# Bridge.net
KiCad netlist of a schematic drawn in EAGLE
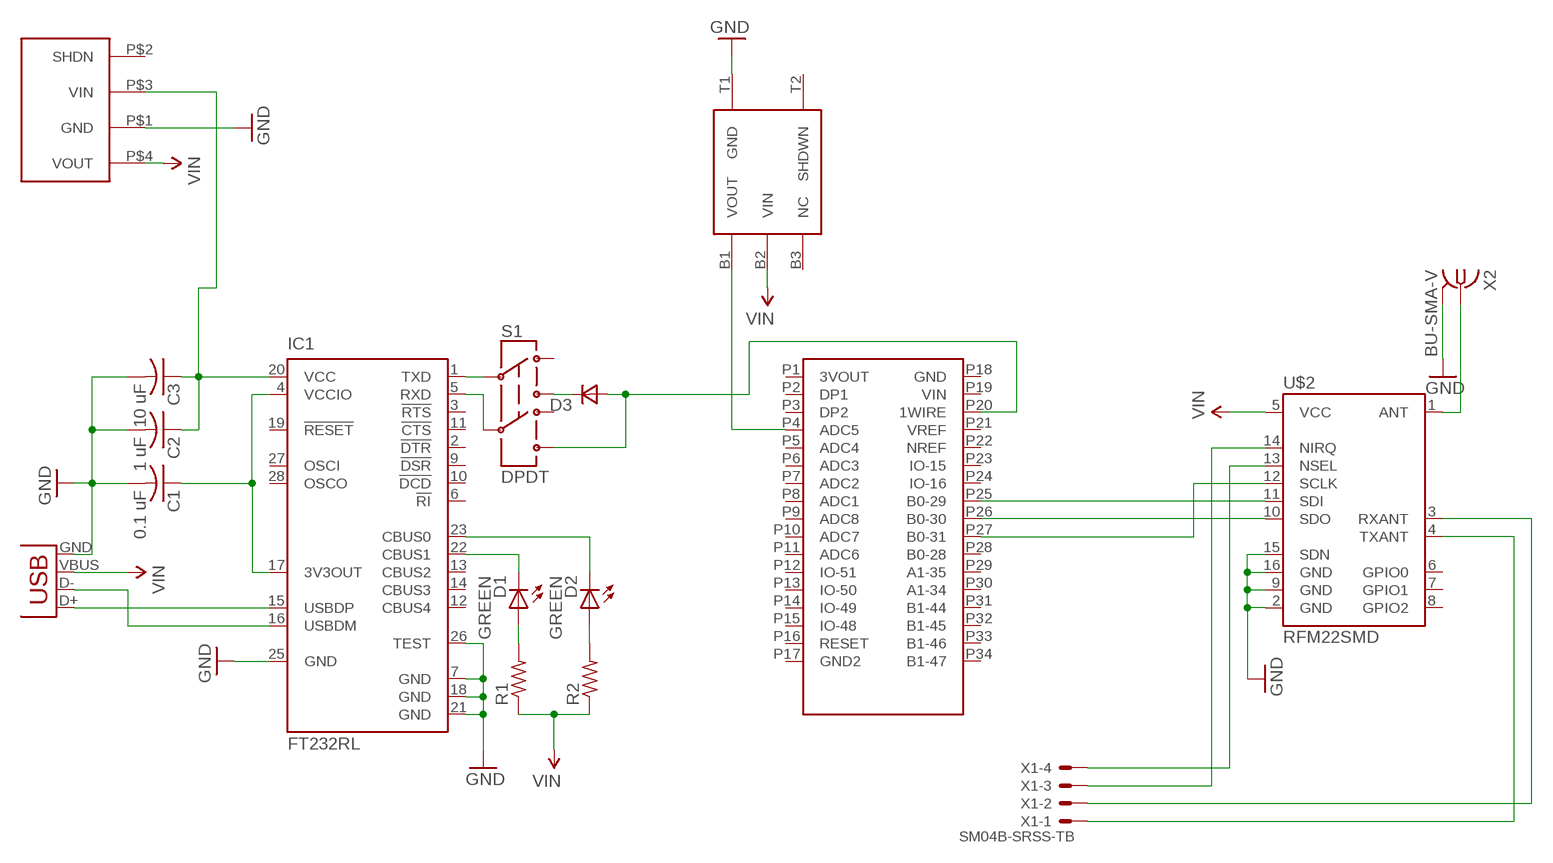
[diagram p0: schematic, sheet 1]

(export (version "E")
  (design (tool "Eeschema 10.0.6"))
  (components
    (comp (ref "C1")
      (value "0.1 uF")
      (footprint "eagle-import:C0805")
      (libsource (lib "eagle-import") (part "C-USC0805"))
    )
    (comp (ref "C2")
      (value "1 uF")
      (footprint "eagle-import:C0805")
      (libsource (lib "eagle-import") (part "C-USC0805"))
    )
    (comp (ref "C3")
      (value "10 uF")
      (footprint "eagle-import:C0805")
      (libsource (lib "eagle-import") (part "C-USC0805"))
    )
    (comp (ref "D1")
      (value "GREEN")
      (footprint "eagle-import:LED-0603")
      (libsource (lib "eagle-import") (part "LED-GREEN0603"))
    )
    (comp (ref "D2")
      (value "GREEN")
      (footprint "eagle-import:LED-0603")
      (libsource (lib "eagle-import") (part "LED-GREEN0603"))
    )
    (comp (ref "D3")
      (value "DSOD323")
      (footprint "eagle-import:SOD323")
      (fields (field (name "MPN") "CDSOD323-T05C"))
      (libsource (lib "eagle-import") (part "DSOD323"))
    )
    (comp (ref "IC1")
      (value "FT232RL")
      (footprint "eagle-import:SSOP28")
      (libsource (lib "eagle-import") (part "FT232RL"))
    )
    (comp (ref "JP1")
      (value "USBSMD")
      (footprint "eagle-import:USB-MINIB")
      (libsource (lib "eagle-import") (part "USBSMD"))
    )
    (comp (ref "R1")
      (value "R-US_R0603")
      (footprint "eagle-import:R0603")
      (libsource (lib "eagle-import") (part "R-US_R0603"))
    )
    (comp (ref "R2")
      (value "R-US_R0603")
      (footprint "eagle-import:R0603")
      (libsource (lib "eagle-import") (part "R-US_R0603"))
    )
    (comp (ref "S1")
      (value "DPDT")
      (footprint "eagle-import:AYZ0202")
      (libsource (lib "eagle-import") (part "SWITCH-DPDTAYZ0202"))
    )
    (comp (ref "U$1")
      (value "APP_CORE")
      (footprint "eagle-import:APPCORE_RECEIVER")
      (libsource (lib "eagle-import") (part "APP_CORE"))
    )
    (comp (ref "U$2")
      (value "RFM22SMD")
      (footprint "eagle-import:RFM22-XXX-S2")
      (libsource (lib "eagle-import") (part "RFM22SMD"))
    )
    (comp (ref "U$3")
      (value "TMP36")
      (footprint "eagle-import:SOT-23-5")
      (libsource (lib "eagle-import") (part "TMP36"))
    )
    (comp (ref "U$6")
      (value "57V8F3_EXT")
      (footprint "eagle-import:S7V8F3_EXT")
      (libsource (lib "eagle-import") (part "57V8F3_EXT"))
    )
    (comp (ref "X1")
      (value "SM04B-SRSS-TB")
      (footprint "eagle-import:SM04B-SRSS-TB")
      (libsource (lib "eagle-import") (part "?M04B-SRSS-TBS"))
    )
    (comp (ref "X2")
      (value "BU-SMA-V")
      (footprint "eagle-import:BU-SMA-V")
      (libsource (lib "eagle-import") (part "BU-SMA-V"))
    )
  )
  (nets
    (net (code "1") (name "GND") (class "Default")
      (node (ref "C1") (pin "2") (pinfunction "2_2") (pintype "passive"))
      (node (ref "C2") (pin "2") (pinfunction "2_2") (pintype "passive"))
      (node (ref "C3") (pin "2") (pinfunction "2_2") (pintype "passive"))
      (node (ref "IC1") (pin "18") (pinfunction "GND_18") (pintype "power_in"))
      (node (ref "IC1") (pin "21") (pinfunction "GND_21") (pintype "power_in"))
      (node (ref "IC1") (pin "25") (pinfunction "GND_25") (pintype "power_in"))
      (node (ref "IC1") (pin "26") (pinfunction "TEST_26") (pintype "input"))
      (node (ref "IC1") (pin "7") (pinfunction "GND_7") (pintype "power_in"))
      (node (ref "JP1") (pin "GND") (pinfunction "GND_GND") (pintype "bidirectional"))
      (node (ref "U$2") (pin "15") (pinfunction "SDN_15") (pintype "input"))
      (node (ref "U$2") (pin "16") (pinfunction "GND_16") (pintype "power_in"))
      (node (ref "U$2") (pin "2") (pinfunction "GND_2") (pintype "power_in"))
      (node (ref "U$2") (pin "9") (pinfunction "GND_9") (pintype "power_in"))
      (node (ref "U$3") (pin "T1") (pinfunction "GND_T1") (pintype "bidirectional"))
      (node (ref "U$6") (pin "P$1") (pinfunction "GND_P$1") (pintype "bidirectional"))
      (node (ref "X2") (pin "2") (pinfunction "2_2") (pintype "passive"))
      (node (ref "X2") (pin "3") (pinfunction "2_3") (pintype "passive"))
      (node (ref "X2") (pin "4") (pinfunction "2_4") (pintype "passive"))
      (node (ref "X2") (pin "5") (pinfunction "2_5") (pintype "passive"))
    )
    (net (code "2") (name "Net-(D1-PadA)") (class "Default")
      (node (ref "D1") (pin "A") (pinfunction "A_A") (pintype "passive"))
      (node (ref "R1") (pin "2") (pinfunction "2_2") (pintype "passive"))
    )
    (net (code "3") (name "Net-(D2-PadA)") (class "Default")
      (node (ref "D2") (pin "A") (pinfunction "A_A") (pintype "passive"))
      (node (ref "R2") (pin "2") (pinfunction "2_2") (pintype "passive"))
    )
    (net (code "4") (name "Net-(D3-A)") (class "Default")
      (node (ref "D3") (pin "2") (pinfunction "A_2") (pintype "passive"))
      (node (ref "S1") (pin "6") (pinfunction "6_6") (pintype "bidirectional"))
      (node (ref "U$1") (pin "P20") (pinfunction "1WIRE_P20") (pintype "bidirectional"))
    )
    (net (code "5") (name "Net-(D3-C)") (class "Default")
      (node (ref "D3") (pin "1") (pinfunction "C_1") (pintype "passive"))
      (node (ref "S1") (pin "3") (pinfunction "3_3") (pintype "bidirectional"))
    )
    (net (code "6") (name "Net-(IC1-3V3OUT)") (class "Default")
      (node (ref "C1") (pin "1") (pinfunction "1_1") (pintype "passive"))
      (node (ref "IC1") (pin "17") (pinfunction "3V3OUT_17") (pintype "output"))
      (node (ref "IC1") (pin "4") (pinfunction "VCCIO_4") (pintype "power_in"))
    )
    (net (code "7") (name "Net-(IC1-CBUS0)") (class "Default")
      (node (ref "D2") (pin "C") (pinfunction "C_C") (pintype "passive"))
      (node (ref "IC1") (pin "23") (pinfunction "CBUS0_23") (pintype "bidirectional"))
    )
    (net (code "8") (name "Net-(IC1-CBUS1)") (class "Default")
      (node (ref "D1") (pin "C") (pinfunction "C_C") (pintype "passive"))
      (node (ref "IC1") (pin "22") (pinfunction "CBUS1_22") (pintype "bidirectional"))
    )
    (net (code "9") (name "Net-(IC1-RXD)") (class "Default")
      (node (ref "IC1") (pin "5") (pinfunction "RXD_5") (pintype "input"))
      (node (ref "S1") (pin "5") (pinfunction "5_5") (pintype "bidirectional"))
    )
    (net (code "10") (name "Net-(IC1-TXD)") (class "Default")
      (node (ref "IC1") (pin "1") (pinfunction "TXD_1") (pintype "output"))
      (node (ref "S1") (pin "2") (pinfunction "2_2") (pintype "bidirectional"))
    )
    (net (code "11") (name "Net-(IC1-USBDM)") (class "Default")
      (node (ref "IC1") (pin "16") (pinfunction "USBDM_16") (pintype "bidirectional"))
      (node (ref "JP1") (pin "D-") (pinfunction "D-_D-") (pintype "bidirectional"))
    )
    (net (code "12") (name "Net-(IC1-USBDP)") (class "Default")
      (node (ref "IC1") (pin "15") (pinfunction "USBDP_15") (pintype "bidirectional"))
      (node (ref "JP1") (pin "D+") (pinfunction "D+_D+") (pintype "bidirectional"))
    )
    (net (code "13") (name "Net-(IC1-VCC)") (class "Default")
      (node (ref "C2") (pin "1") (pinfunction "1_1") (pintype "passive"))
      (node (ref "C3") (pin "1") (pinfunction "1_1") (pintype "passive"))
      (node (ref "IC1") (pin "20") (pinfunction "VCC_20") (pintype "power_in"))
      (node (ref "U$6") (pin "P$3") (pinfunction "VIN_P$3") (pintype "bidirectional"))
    )
    (net (code "14") (name "Net-(U$1-ADC5)") (class "Default")
      (node (ref "U$1") (pin "P4") (pinfunction "ADC5_P4") (pintype "bidirectional"))
      (node (ref "U$3") (pin "B1") (pinfunction "VOUT_B1") (pintype "bidirectional"))
    )
    (net (code "15") (name "Net-(U$1-B0-29)") (class "Default")
      (node (ref "U$1") (pin "P25") (pinfunction "B0-29_P25") (pintype "bidirectional"))
      (node (ref "U$2") (pin "11") (pinfunction "SDI_11") (pintype "input"))
    )
    (net (code "16") (name "Net-(U$1-B0-30)") (class "Default")
      (node (ref "U$1") (pin "P26") (pinfunction "B0-30_P26") (pintype "bidirectional"))
      (node (ref "U$2") (pin "10") (pinfunction "SDO_10") (pintype "output"))
    )
    (net (code "17") (name "Net-(U$1-B0-31)") (class "Default")
      (node (ref "U$1") (pin "P27") (pinfunction "B0-31_P27") (pintype "bidirectional"))
      (node (ref "U$2") (pin "12") (pinfunction "SCLK_12") (pintype "input"))
    )
    (net (code "18") (name "Net-(U$2-ANT)") (class "Default")
      (node (ref "U$2") (pin "1") (pinfunction "ANT_1") (pintype "bidirectional"))
      (node (ref "X2") (pin "1") (pinfunction "1_1") (pintype "passive"))
    )
    (net (code "19") (name "Net-(U$2-NIRQ)") (class "Default")
      (node (ref "U$2") (pin "14") (pinfunction "NIRQ_14") (pintype "output"))
      (node (ref "X1") (pin "3") (pinfunction "S_3") (pintype "passive"))
    )
    (net (code "20") (name "Net-(U$2-NSEL)") (class "Default")
      (node (ref "U$2") (pin "13") (pinfunction "NSEL_13") (pintype "input"))
      (node (ref "X1") (pin "4") (pinfunction "S_4") (pintype "passive"))
    )
    (net (code "21") (name "Net-(U$2-RXANT)") (class "Default")
      (node (ref "U$2") (pin "3") (pinfunction "RXANT_3") (pintype "input"))
      (node (ref "X1") (pin "2") (pinfunction "S_2") (pintype "passive"))
    )
    (net (code "22") (name "Net-(U$2-TXANT)") (class "Default")
      (node (ref "U$2") (pin "4") (pinfunction "TXANT_4") (pintype "input"))
      (node (ref "X1") (pin "1") (pinfunction "S_1") (pintype "passive"))
    )
    (net (code "23") (name "VIN") (class "Default")
      (node (ref "JP1") (pin "VBUS") (pinfunction "VBUS_VBUS") (pintype "bidirectional"))
      (node (ref "R1") (pin "1") (pinfunction "1_1") (pintype "passive"))
      (node (ref "R2") (pin "1") (pinfunction "1_1") (pintype "passive"))
      (node (ref "U$2") (pin "5") (pinfunction "VCC_5") (pintype "bidirectional"))
      (node (ref "U$3") (pin "B2") (pinfunction "VIN_B2") (pintype "bidirectional"))
      (node (ref "U$6") (pin "P$4") (pinfunction "VOUT_P$4") (pintype "bidirectional"))
    )
    (net (code "24") (name "unconnected-(IC1-CBUS2-Pad13)") (class "Default")
      (node (ref "IC1") (pin "13") (pinfunction "CBUS2_13") (pintype "bidirectional"))
    )
    (net (code "25") (name "unconnected-(IC1-CBUS3-Pad14)") (class "Default")
      (node (ref "IC1") (pin "14") (pinfunction "CBUS3_14") (pintype "bidirectional"))
    )
    (net (code "26") (name "unconnected-(IC1-CBUS4-Pad12)") (class "Default")
      (node (ref "IC1") (pin "12") (pinfunction "CBUS4_12") (pintype "bidirectional"))
    )
    (net (code "27") (name "unconnected-(IC1-OSCI-Pad27)") (class "Default")
      (node (ref "IC1") (pin "27") (pinfunction "OSCI_27") (pintype "input"))
    )
    (net (code "28") (name "unconnected-(IC1-OSCO-Pad28)") (class "Default")
      (node (ref "IC1") (pin "28") (pinfunction "OSCO_28") (pintype "output"))
    )
    (net (code "29") (name "unconnected-(IC1-~{CTS}-Pad11)") (class "Default")
      (node (ref "IC1") (pin "11") (pinfunction "~{CTS}_11") (pintype "input"))
    )
    (net (code "30") (name "unconnected-(IC1-~{DCD}-Pad10)") (class "Default")
      (node (ref "IC1") (pin "10") (pinfunction "~{DCD}_10") (pintype "input"))
    )
    (net (code "31") (name "unconnected-(IC1-~{DSR}-Pad9)") (class "Default")
      (node (ref "IC1") (pin "9") (pinfunction "~{DSR}_9") (pintype "input"))
    )
    (net (code "32") (name "unconnected-(IC1-~{DTR}-Pad2)") (class "Default")
      (node (ref "IC1") (pin "2") (pinfunction "~{DTR}_2") (pintype "output"))
    )
    (net (code "33") (name "unconnected-(IC1-~{RESET}-Pad19)") (class "Default")
      (node (ref "IC1") (pin "19") (pinfunction "~{RESET}_19") (pintype "input"))
    )
    (net (code "34") (name "unconnected-(IC1-~{RI}-Pad6)") (class "Default")
      (node (ref "IC1") (pin "6") (pinfunction "~{RI}_6") (pintype "input"))
    )
    (net (code "35") (name "unconnected-(IC1-~{RTS}-Pad3)") (class "Default")
      (node (ref "IC1") (pin "3") (pinfunction "~{RTS}_3") (pintype "output"))
    )
    (net (code "36") (name "unconnected-(S1-Pad1)") (class "Default")
      (node (ref "S1") (pin "1") (pinfunction "1_1") (pintype "bidirectional"))
    )
    (net (code "37") (name "unconnected-(S1-Pad4)") (class "Default")
      (node (ref "S1") (pin "4") (pinfunction "4_4") (pintype "bidirectional"))
    )
    (net (code "38") (name "unconnected-(U$1-3VOUT-PadP1)") (class "Default")
      (node (ref "U$1") (pin "P1") (pinfunction "3VOUT_P1") (pintype "bidirectional"))
    )
    (net (code "39") (name "unconnected-(U$1-A1-34-PadP30)") (class "Default")
      (node (ref "U$1") (pin "P30") (pinfunction "A1-34_P30") (pintype "bidirectional"))
    )
    (net (code "40") (name "unconnected-(U$1-A1-35-PadP29)") (class "Default")
      (node (ref "U$1") (pin "P29") (pinfunction "A1-35_P29") (pintype "bidirectional"))
    )
    (net (code "41") (name "unconnected-(U$1-ADC1-PadP8)") (class "Default")
      (node (ref "U$1") (pin "P8") (pinfunction "ADC1_P8") (pintype "bidirectional"))
    )
    (net (code "42") (name "unconnected-(U$1-ADC2-PadP7)") (class "Default")
      (node (ref "U$1") (pin "P7") (pinfunction "ADC2_P7") (pintype "bidirectional"))
    )
    (net (code "43") (name "unconnected-(U$1-ADC3-PadP6)") (class "Default")
      (node (ref "U$1") (pin "P6") (pinfunction "ADC3_P6") (pintype "bidirectional"))
    )
    (net (code "44") (name "unconnected-(U$1-ADC4-PadP5)") (class "Default")
      (node (ref "U$1") (pin "P5") (pinfunction "ADC4_P5") (pintype "bidirectional"))
    )
    (net (code "45") (name "unconnected-(U$1-ADC6-PadP11)") (class "Default")
      (node (ref "U$1") (pin "P11") (pinfunction "ADC6_P11") (pintype "bidirectional"))
    )
    (net (code "46") (name "unconnected-(U$1-ADC7-PadP10)") (class "Default")
      (node (ref "U$1") (pin "P10") (pinfunction "ADC7_P10") (pintype "bidirectional"))
    )
    (net (code "47") (name "unconnected-(U$1-ADC8-PadP9)") (class "Default")
      (node (ref "U$1") (pin "P9") (pinfunction "ADC8_P9") (pintype "bidirectional"))
    )
    (net (code "48") (name "unconnected-(U$1-B0-28-PadP28)") (class "Default")
      (node (ref "U$1") (pin "P28") (pinfunction "B0-28_P28") (pintype "bidirectional"))
    )
    (net (code "49") (name "unconnected-(U$1-B1-44-PadP31)") (class "Default")
      (node (ref "U$1") (pin "P31") (pinfunction "B1-44_P31") (pintype "bidirectional"))
    )
    (net (code "50") (name "unconnected-(U$1-B1-45-PadP32)") (class "Default")
      (node (ref "U$1") (pin "P32") (pinfunction "B1-45_P32") (pintype "bidirectional"))
    )
    (net (code "51") (name "unconnected-(U$1-B1-46-PadP33)") (class "Default")
      (node (ref "U$1") (pin "P33") (pinfunction "B1-46_P33") (pintype "bidirectional"))
    )
    (net (code "52") (name "unconnected-(U$1-B1-47-PadP34)") (class "Default")
      (node (ref "U$1") (pin "P34") (pinfunction "B1-47_P34") (pintype "bidirectional"))
    )
    (net (code "53") (name "unconnected-(U$1-DP1-PadP2)") (class "Default")
      (node (ref "U$1") (pin "P2") (pinfunction "DP1_P2") (pintype "bidirectional"))
    )
    (net (code "54") (name "unconnected-(U$1-DP2-PadP3)") (class "Default")
      (node (ref "U$1") (pin "P3") (pinfunction "DP2_P3") (pintype "bidirectional"))
    )
    (net (code "55") (name "unconnected-(U$1-GND-PadP18)") (class "Default")
      (node (ref "U$1") (pin "P18") (pinfunction "GND_P18") (pintype "bidirectional"))
    )
    (net (code "56") (name "unconnected-(U$1-GND2-PadP17)") (class "Default")
      (node (ref "U$1") (pin "P17") (pinfunction "GND2_P17") (pintype "bidirectional"))
    )
    (net (code "57") (name "unconnected-(U$1-IO-15-PadP23)") (class "Default")
      (node (ref "U$1") (pin "P23") (pinfunction "IO-15_P23") (pintype "bidirectional"))
    )
    (net (code "58") (name "unconnected-(U$1-IO-16-PadP24)") (class "Default")
      (node (ref "U$1") (pin "P24") (pinfunction "IO-16_P24") (pintype "bidirectional"))
    )
    (net (code "59") (name "unconnected-(U$1-IO-48-PadP15)") (class "Default")
      (node (ref "U$1") (pin "P15") (pinfunction "IO-48_P15") (pintype "bidirectional"))
    )
    (net (code "60") (name "unconnected-(U$1-IO-49-PadP14)") (class "Default")
      (node (ref "U$1") (pin "P14") (pinfunction "IO-49_P14") (pintype "bidirectional"))
    )
    (net (code "61") (name "unconnected-(U$1-IO-50-PadP13)") (class "Default")
      (node (ref "U$1") (pin "P13") (pinfunction "IO-50_P13") (pintype "bidirectional"))
    )
    (net (code "62") (name "unconnected-(U$1-IO-51-PadP12)") (class "Default")
      (node (ref "U$1") (pin "P12") (pinfunction "IO-51_P12") (pintype "bidirectional"))
    )
    (net (code "63") (name "unconnected-(U$1-NREF-PadP22)") (class "Default")
      (node (ref "U$1") (pin "P22") (pinfunction "NREF_P22") (pintype "bidirectional"))
    )
    (net (code "64") (name "unconnected-(U$1-RESET-PadP16)") (class "Default")
      (node (ref "U$1") (pin "P16") (pinfunction "RESET_P16") (pintype "bidirectional"))
    )
    (net (code "65") (name "unconnected-(U$1-VIN-PadP19)") (class "Default")
      (node (ref "U$1") (pin "P19") (pinfunction "VIN_P19") (pintype "bidirectional"))
    )
    (net (code "66") (name "unconnected-(U$1-VREF-PadP21)") (class "Default")
      (node (ref "U$1") (pin "P21") (pinfunction "VREF_P21") (pintype "bidirectional"))
    )
    (net (code "67") (name "unconnected-(U$2-GPIO0-Pad6)") (class "Default")
      (node (ref "U$2") (pin "6") (pinfunction "GPIO0_6") (pintype "bidirectional"))
    )
    (net (code "68") (name "unconnected-(U$2-GPIO1-Pad7)") (class "Default")
      (node (ref "U$2") (pin "7") (pinfunction "GPIO1_7") (pintype "bidirectional"))
    )
    (net (code "69") (name "unconnected-(U$2-GPIO2-Pad8)") (class "Default")
      (node (ref "U$2") (pin "8") (pinfunction "GPIO2_8") (pintype "bidirectional"))
    )
    (net (code "70") (name "unconnected-(U$3-NC-PadB3)") (class "Default")
      (node (ref "U$3") (pin "B3") (pinfunction "NC_B3") (pintype "bidirectional"))
    )
    (net (code "71") (name "unconnected-(U$3-SHDWN-PadT2)") (class "Default")
      (node (ref "U$3") (pin "T2") (pinfunction "SHDWN_T2") (pintype "bidirectional"))
    )
    (net (code "72") (name "unconnected-(U$6-SHDN-PadP$2)") (class "Default")
      (node (ref "U$6") (pin "P$2") (pinfunction "SHDN_P$2") (pintype "bidirectional"))
    )
  )
)
